# untitled.net
KiCad netlist of a schematic drawn in EAGLE
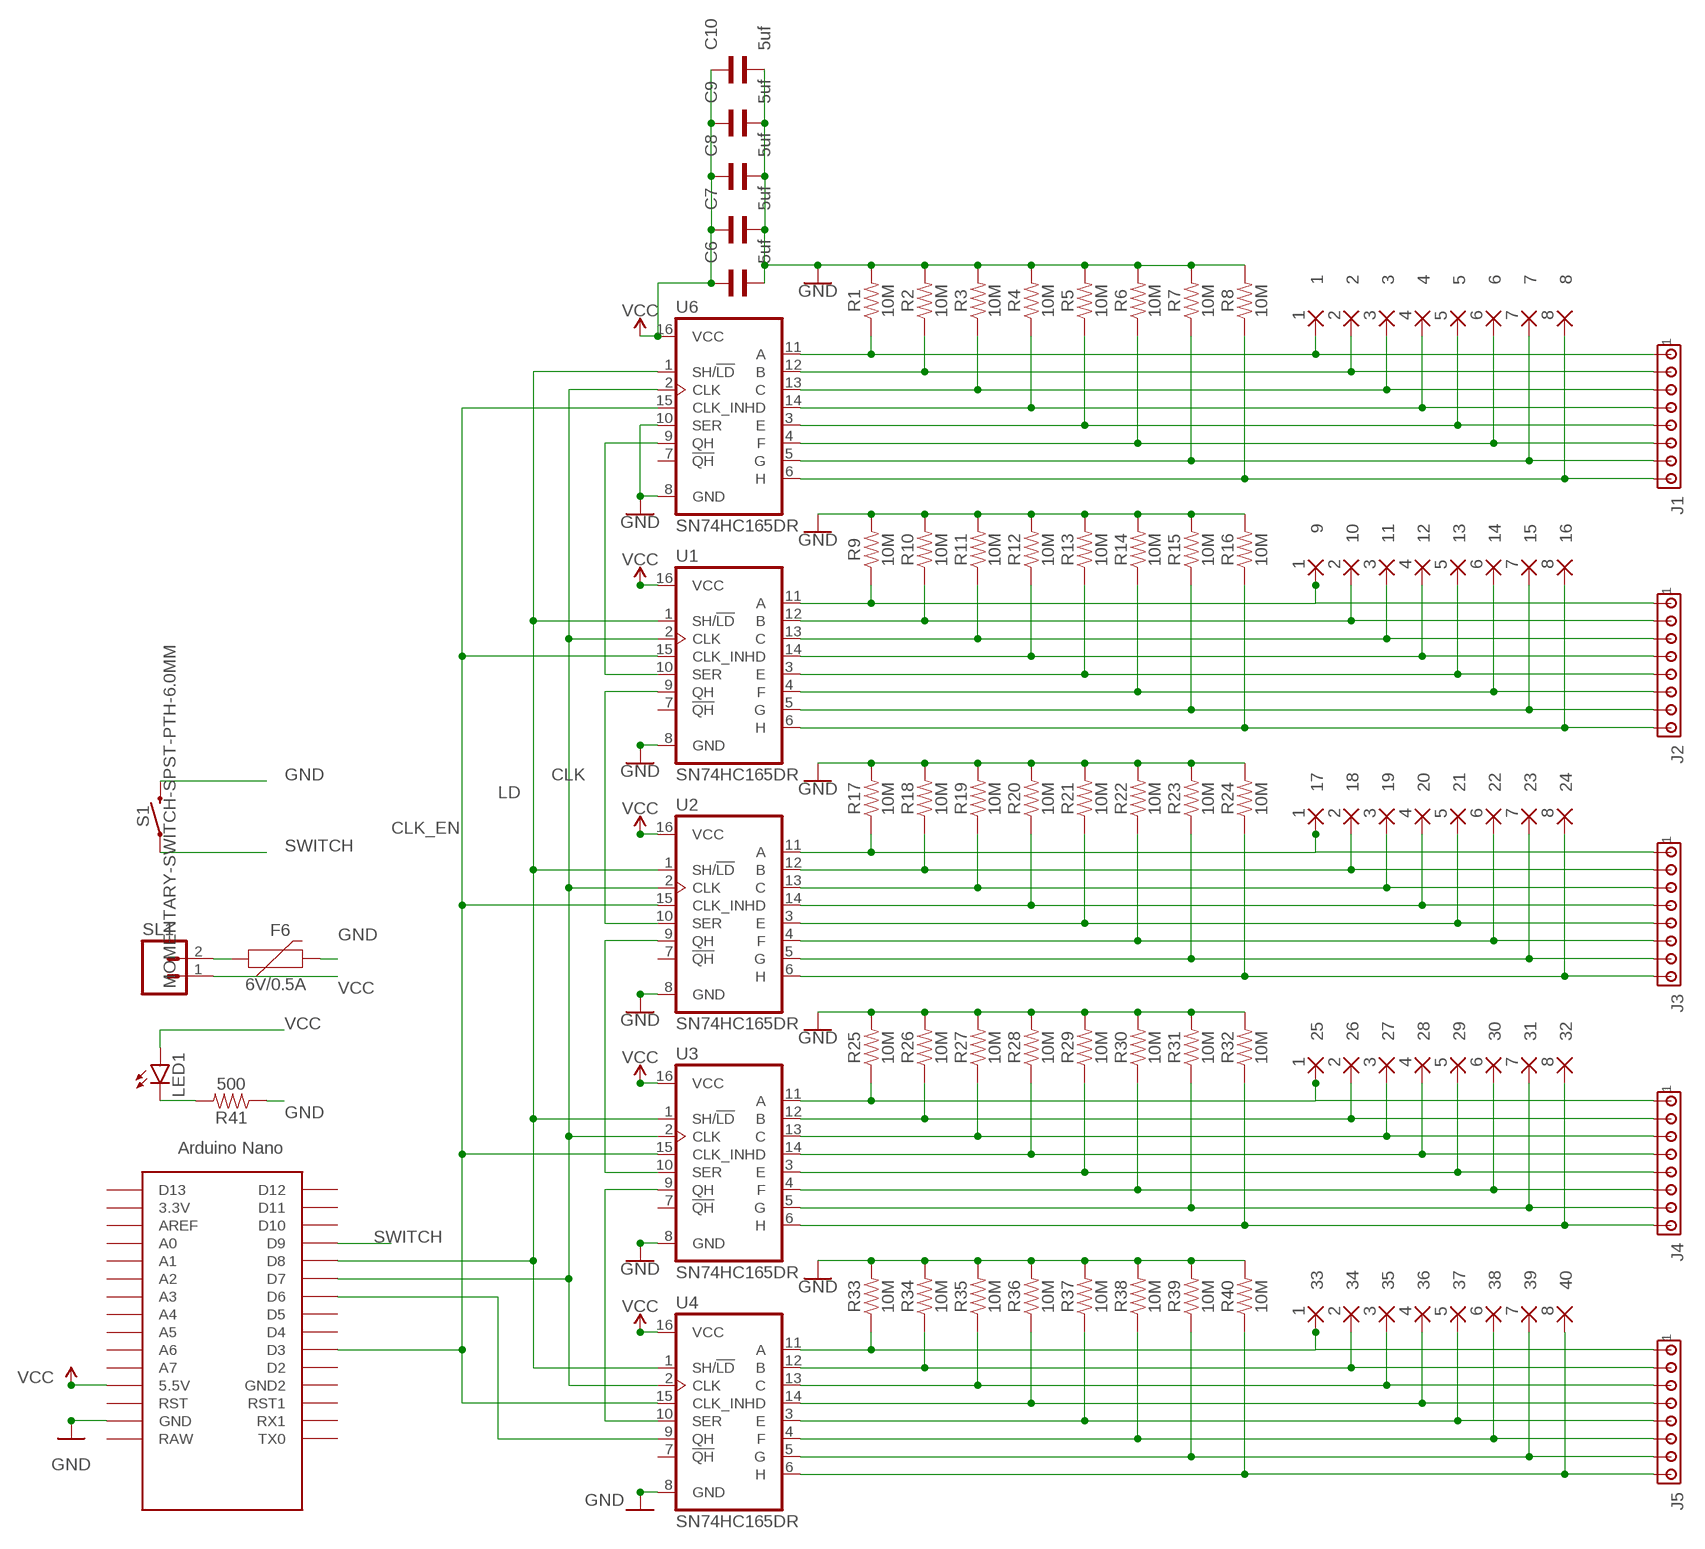
[diagram p0: schematic, sheet 1]

(export (version "E")
  (design (tool "Eeschema 10.0.6"))
  (components
    (comp (ref "1")
      (value "1")
      (footprint "eagle-import:5-1,8")
      (libsource (lib "eagle-import") (part "WIREPADSMD5-1,8"))
    )
    (comp (ref "2")
      (value "2")
      (footprint "eagle-import:5-1,8")
      (libsource (lib "eagle-import") (part "WIREPADSMD5-1,8"))
    )
    (comp (ref "3")
      (value "3")
      (footprint "eagle-import:5-1,8")
      (libsource (lib "eagle-import") (part "WIREPADSMD5-1,8"))
    )
    (comp (ref "4")
      (value "4")
      (footprint "eagle-import:5-1,8")
      (libsource (lib "eagle-import") (part "WIREPADSMD5-1,8"))
    )
    (comp (ref "5")
      (value "5")
      (footprint "eagle-import:5-1,8")
      (libsource (lib "eagle-import") (part "WIREPADSMD5-1,8"))
    )
    (comp (ref "6")
      (value "6")
      (footprint "eagle-import:5-1,8")
      (libsource (lib "eagle-import") (part "WIREPADSMD5-1,8"))
    )
    (comp (ref "7")
      (value "7")
      (footprint "eagle-import:5-1,8")
      (libsource (lib "eagle-import") (part "WIREPADSMD5-1,8"))
    )
    (comp (ref "8")
      (value "8")
      (footprint "eagle-import:5-1,8")
      (libsource (lib "eagle-import") (part "WIREPADSMD5-1,8"))
    )
    (comp (ref "9")
      (value "1")
      (footprint "eagle-import:5-1,8")
      (libsource (lib "eagle-import") (part "WIREPADSMD5-1,8"))
    )
    (comp (ref "10")
      (value "2")
      (footprint "eagle-import:5-1,8")
      (libsource (lib "eagle-import") (part "WIREPADSMD5-1,8"))
    )
    (comp (ref "11")
      (value "3")
      (footprint "eagle-import:5-1,8")
      (libsource (lib "eagle-import") (part "WIREPADSMD5-1,8"))
    )
    (comp (ref "12")
      (value "4")
      (footprint "eagle-import:5-1,8")
      (libsource (lib "eagle-import") (part "WIREPADSMD5-1,8"))
    )
    (comp (ref "13")
      (value "5")
      (footprint "eagle-import:5-1,8")
      (libsource (lib "eagle-import") (part "WIREPADSMD5-1,8"))
    )
    (comp (ref "14")
      (value "6")
      (footprint "eagle-import:5-1,8")
      (libsource (lib "eagle-import") (part "WIREPADSMD5-1,8"))
    )
    (comp (ref "15")
      (value "7")
      (footprint "eagle-import:5-1,8")
      (libsource (lib "eagle-import") (part "WIREPADSMD5-1,8"))
    )
    (comp (ref "16")
      (value "8")
      (footprint "eagle-import:5-1,8")
      (libsource (lib "eagle-import") (part "WIREPADSMD5-1,8"))
    )
    (comp (ref "17")
      (value "1")
      (footprint "eagle-import:5-1,8")
      (libsource (lib "eagle-import") (part "WIREPADSMD5-1,8"))
    )
    (comp (ref "18")
      (value "2")
      (footprint "eagle-import:5-1,8")
      (libsource (lib "eagle-import") (part "WIREPADSMD5-1,8"))
    )
    (comp (ref "19")
      (value "3")
      (footprint "eagle-import:5-1,8")
      (libsource (lib "eagle-import") (part "WIREPADSMD5-1,8"))
    )
    (comp (ref "20")
      (value "4")
      (footprint "eagle-import:5-1,8")
      (libsource (lib "eagle-import") (part "WIREPADSMD5-1,8"))
    )
    (comp (ref "21")
      (value "5")
      (footprint "eagle-import:5-1,8")
      (libsource (lib "eagle-import") (part "WIREPADSMD5-1,8"))
    )
    (comp (ref "22")
      (value "6")
      (footprint "eagle-import:5-1,8")
      (libsource (lib "eagle-import") (part "WIREPADSMD5-1,8"))
    )
    (comp (ref "23")
      (value "7")
      (footprint "eagle-import:5-1,8")
      (libsource (lib "eagle-import") (part "WIREPADSMD5-1,8"))
    )
    (comp (ref "24")
      (value "8")
      (footprint "eagle-import:5-1,8")
      (libsource (lib "eagle-import") (part "WIREPADSMD5-1,8"))
    )
    (comp (ref "25")
      (value "1")
      (footprint "eagle-import:5-1,8")
      (libsource (lib "eagle-import") (part "WIREPADSMD5-1,8"))
    )
    (comp (ref "26")
      (value "2")
      (footprint "eagle-import:5-1,8")
      (libsource (lib "eagle-import") (part "WIREPADSMD5-1,8"))
    )
    (comp (ref "27")
      (value "3")
      (footprint "eagle-import:5-1,8")
      (libsource (lib "eagle-import") (part "WIREPADSMD5-1,8"))
    )
    (comp (ref "28")
      (value "4")
      (footprint "eagle-import:5-1,8")
      (libsource (lib "eagle-import") (part "WIREPADSMD5-1,8"))
    )
    (comp (ref "29")
      (value "5")
      (footprint "eagle-import:5-1,8")
      (libsource (lib "eagle-import") (part "WIREPADSMD5-1,8"))
    )
    (comp (ref "30")
      (value "6")
      (footprint "eagle-import:5-1,8")
      (libsource (lib "eagle-import") (part "WIREPADSMD5-1,8"))
    )
    (comp (ref "31")
      (value "7")
      (footprint "eagle-import:5-1,8")
      (libsource (lib "eagle-import") (part "WIREPADSMD5-1,8"))
    )
    (comp (ref "32")
      (value "8")
      (footprint "eagle-import:5-1,8")
      (libsource (lib "eagle-import") (part "WIREPADSMD5-1,8"))
    )
    (comp (ref "33")
      (value "1")
      (footprint "eagle-import:5-1,8")
      (libsource (lib "eagle-import") (part "WIREPADSMD5-1,8"))
    )
    (comp (ref "34")
      (value "2")
      (footprint "eagle-import:5-1,8")
      (libsource (lib "eagle-import") (part "WIREPADSMD5-1,8"))
    )
    (comp (ref "35")
      (value "3")
      (footprint "eagle-import:5-1,8")
      (libsource (lib "eagle-import") (part "WIREPADSMD5-1,8"))
    )
    (comp (ref "36")
      (value "4")
      (footprint "eagle-import:5-1,8")
      (libsource (lib "eagle-import") (part "WIREPADSMD5-1,8"))
    )
    (comp (ref "37")
      (value "5")
      (footprint "eagle-import:5-1,8")
      (libsource (lib "eagle-import") (part "WIREPADSMD5-1,8"))
    )
    (comp (ref "38")
      (value "6")
      (footprint "eagle-import:5-1,8")
      (libsource (lib "eagle-import") (part "WIREPADSMD5-1,8"))
    )
    (comp (ref "39")
      (value "7")
      (footprint "eagle-import:5-1,8")
      (libsource (lib "eagle-import") (part "WIREPADSMD5-1,8"))
    )
    (comp (ref "40")
      (value "8")
      (footprint "eagle-import:5-1,8")
      (libsource (lib "eagle-import") (part "WIREPADSMD5-1,8"))
    )
    (comp (ref "C6")
      (value "5uf")
      (footprint "eagle-import:WCAP-CSGP_1206")
      (libsource (lib "eagle-import") (part "WCAP-CSGP_1206_885012208119"))
    )
    (comp (ref "C7")
      (value "5uf")
      (footprint "eagle-import:WCAP-CSGP_1206")
      (libsource (lib "eagle-import") (part "WCAP-CSGP_1206_885012208119"))
    )
    (comp (ref "C8")
      (value "5uf")
      (footprint "eagle-import:WCAP-CSGP_1206")
      (libsource (lib "eagle-import") (part "WCAP-CSGP_1206_885012208119"))
    )
    (comp (ref "C9")
      (value "5uf")
      (footprint "eagle-import:WCAP-CSGP_1206")
      (libsource (lib "eagle-import") (part "WCAP-CSGP_1206_885012208119"))
    )
    (comp (ref "C10")
      (value "5uf")
      (footprint "eagle-import:WCAP-CSGP_1206")
      (libsource (lib "eagle-import") (part "WCAP-CSGP_1206_885012208119"))
    )
    (comp (ref "F6")
      (value "6V/0.5A")
      (footprint "eagle-import:1206")
      (libsource (lib "eagle-import") (part "PPTC_HALF-AMP"))
    )
    (comp (ref "J1")
      (value "MTA08-100")
      (footprint "eagle-import:10X08MTA")
      (libsource (lib "eagle-import") (part "MTA08-100"))
    )
    (comp (ref "J2")
      (value "MTA08-100")
      (footprint "eagle-import:10X08MTA")
      (libsource (lib "eagle-import") (part "MTA08-100"))
    )
    (comp (ref "J3")
      (value "MTA08-100")
      (footprint "eagle-import:10X08MTA")
      (libsource (lib "eagle-import") (part "MTA08-100"))
    )
    (comp (ref "J4")
      (value "MTA08-100")
      (footprint "eagle-import:10X08MTA")
      (libsource (lib "eagle-import") (part "MTA08-100"))
    )
    (comp (ref "J5")
      (value "MTA08-100")
      (footprint "eagle-import:10X08MTA")
      (libsource (lib "eagle-import") (part "MTA08-100"))
    )
    (comp (ref "LED1")
      (value "LEDSML0805")
      (footprint "eagle-import:SML0805")
      (libsource (lib "eagle-import") (part "LEDSML0805"))
    )
    (comp (ref "R1")
      (value "10M")
      (footprint "eagle-import:0603")
      (libsource (lib "eagle-import") (part "10MOHM-0603-1/10W-5%"))
    )
    (comp (ref "R2")
      (value "10M")
      (footprint "eagle-import:0603")
      (libsource (lib "eagle-import") (part "10MOHM-0603-1/10W-5%"))
    )
    (comp (ref "R3")
      (value "10M")
      (footprint "eagle-import:0603")
      (libsource (lib "eagle-import") (part "10MOHM-0603-1/10W-5%"))
    )
    (comp (ref "R4")
      (value "10M")
      (footprint "eagle-import:0603")
      (libsource (lib "eagle-import") (part "10MOHM-0603-1/10W-5%"))
    )
    (comp (ref "R5")
      (value "10M")
      (footprint "eagle-import:0603")
      (libsource (lib "eagle-import") (part "10MOHM-0603-1/10W-5%"))
    )
    (comp (ref "R6")
      (value "10M")
      (footprint "eagle-import:0603")
      (libsource (lib "eagle-import") (part "10MOHM-0603-1/10W-5%"))
    )
    (comp (ref "R7")
      (value "10M")
      (footprint "eagle-import:0603")
      (libsource (lib "eagle-import") (part "10MOHM-0603-1/10W-5%"))
    )
    (comp (ref "R8")
      (value "10M")
      (footprint "eagle-import:0603")
      (libsource (lib "eagle-import") (part "10MOHM-0603-1/10W-5%"))
    )
    (comp (ref "R9")
      (value "10M")
      (footprint "eagle-import:0603")
      (libsource (lib "eagle-import") (part "10MOHM-0603-1/10W-5%"))
    )
    (comp (ref "R10")
      (value "10M")
      (footprint "eagle-import:0603")
      (libsource (lib "eagle-import") (part "10MOHM-0603-1/10W-5%"))
    )
    (comp (ref "R11")
      (value "10M")
      (footprint "eagle-import:0603")
      (libsource (lib "eagle-import") (part "10MOHM-0603-1/10W-5%"))
    )
    (comp (ref "R12")
      (value "10M")
      (footprint "eagle-import:0603")
      (libsource (lib "eagle-import") (part "10MOHM-0603-1/10W-5%"))
    )
    (comp (ref "R13")
      (value "10M")
      (footprint "eagle-import:0603")
      (libsource (lib "eagle-import") (part "10MOHM-0603-1/10W-5%"))
    )
    (comp (ref "R14")
      (value "10M")
      (footprint "eagle-import:0603")
      (libsource (lib "eagle-import") (part "10MOHM-0603-1/10W-5%"))
    )
    (comp (ref "R15")
      (value "10M")
      (footprint "eagle-import:0603")
      (libsource (lib "eagle-import") (part "10MOHM-0603-1/10W-5%"))
    )
    (comp (ref "R16")
      (value "10M")
      (footprint "eagle-import:0603")
      (libsource (lib "eagle-import") (part "10MOHM-0603-1/10W-5%"))
    )
    (comp (ref "R17")
      (value "10M")
      (footprint "eagle-import:0603")
      (libsource (lib "eagle-import") (part "10MOHM-0603-1/10W-5%"))
    )
    (comp (ref "R18")
      (value "10M")
      (footprint "eagle-import:0603")
      (libsource (lib "eagle-import") (part "10MOHM-0603-1/10W-5%"))
    )
    (comp (ref "R19")
      (value "10M")
      (footprint "eagle-import:0603")
      (libsource (lib "eagle-import") (part "10MOHM-0603-1/10W-5%"))
    )
    (comp (ref "R20")
      (value "10M")
      (footprint "eagle-import:0603")
      (libsource (lib "eagle-import") (part "10MOHM-0603-1/10W-5%"))
    )
    (comp (ref "R21")
      (value "10M")
      (footprint "eagle-import:0603")
      (libsource (lib "eagle-import") (part "10MOHM-0603-1/10W-5%"))
    )
    (comp (ref "R22")
      (value "10M")
      (footprint "eagle-import:0603")
      (libsource (lib "eagle-import") (part "10MOHM-0603-1/10W-5%"))
    )
    (comp (ref "R23")
      (value "10M")
      (footprint "eagle-import:0603")
      (libsource (lib "eagle-import") (part "10MOHM-0603-1/10W-5%"))
    )
    (comp (ref "R24")
      (value "10M")
      (footprint "eagle-import:0603")
      (libsource (lib "eagle-import") (part "10MOHM-0603-1/10W-5%"))
    )
    (comp (ref "R25")
      (value "10M")
      (footprint "eagle-import:0603")
      (libsource (lib "eagle-import") (part "10MOHM-0603-1/10W-5%"))
    )
    (comp (ref "R26")
      (value "10M")
      (footprint "eagle-import:0603")
      (libsource (lib "eagle-import") (part "10MOHM-0603-1/10W-5%"))
    )
    (comp (ref "R27")
      (value "10M")
      (footprint "eagle-import:0603")
      (libsource (lib "eagle-import") (part "10MOHM-0603-1/10W-5%"))
    )
    (comp (ref "R28")
      (value "10M")
      (footprint "eagle-import:0603")
      (libsource (lib "eagle-import") (part "10MOHM-0603-1/10W-5%"))
    )
    (comp (ref "R29")
      (value "10M")
      (footprint "eagle-import:0603")
      (libsource (lib "eagle-import") (part "10MOHM-0603-1/10W-5%"))
    )
    (comp (ref "R30")
      (value "10M")
      (footprint "eagle-import:0603")
      (libsource (lib "eagle-import") (part "10MOHM-0603-1/10W-5%"))
    )
    (comp (ref "R31")
      (value "10M")
      (footprint "eagle-import:0603")
      (libsource (lib "eagle-import") (part "10MOHM-0603-1/10W-5%"))
    )
    (comp (ref "R32")
      (value "10M")
      (footprint "eagle-import:0603")
      (libsource (lib "eagle-import") (part "10MOHM-0603-1/10W-5%"))
    )
    (comp (ref "R33")
      (value "10M")
      (footprint "eagle-import:0603")
      (libsource (lib "eagle-import") (part "10MOHM-0603-1/10W-5%"))
    )
    (comp (ref "R34")
      (value "10M")
      (footprint "eagle-import:0603")
      (libsource (lib "eagle-import") (part "10MOHM-0603-1/10W-5%"))
    )
    (comp (ref "R35")
      (value "10M")
      (footprint "eagle-import:0603")
      (libsource (lib "eagle-import") (part "10MOHM-0603-1/10W-5%"))
    )
    (comp (ref "R36")
      (value "10M")
      (footprint "eagle-import:0603")
      (libsource (lib "eagle-import") (part "10MOHM-0603-1/10W-5%"))
    )
    (comp (ref "R37")
      (value "10M")
      (footprint "eagle-import:0603")
      (libsource (lib "eagle-import") (part "10MOHM-0603-1/10W-5%"))
    )
    (comp (ref "R38")
      (value "10M")
      (footprint "eagle-import:0603")
      (libsource (lib "eagle-import") (part "10MOHM-0603-1/10W-5%"))
    )
    (comp (ref "R39")
      (value "10M")
      (footprint "eagle-import:0603")
      (libsource (lib "eagle-import") (part "10MOHM-0603-1/10W-5%"))
    )
    (comp (ref "R40")
      (value "10M")
      (footprint "eagle-import:0603")
      (libsource (lib "eagle-import") (part "10MOHM-0603-1/10W-5%"))
    )
    (comp (ref "R41")
      (value "500")
      (footprint "eagle-import:0603")
      (libsource (lib "eagle-import") (part "10MOHM-0603-1/10W-5%"))
    )
    (comp (ref "S1")
      (value "MOMENTARY-SWITCH-SPST-PTH-6.0MM")
      (footprint "eagle-import:TACTILE_SWITCH_PTH_6.0MM")
      (libsource (lib "eagle-import") (part "MOMENTARY-SWITCH-SPST-PTH-6.0MM"))
    )
    (comp (ref "SL1")
      (value "M02")
      (footprint "eagle-import:02P")
      (libsource (lib "eagle-import") (part "M02"))
    )
    (comp (ref "U$1")
      (value "NANO")
      (footprint "eagle-import:NANO")
      (libsource (lib "eagle-import") (part "NANO"))
    )
    (comp (ref "U1")
      (value "SN74HC165DR")
      (footprint "eagle-import:SO16")
      (libsource (lib "eagle-import") (part "74165DHC"))
    )
    (comp (ref "U2")
      (value "SN74HC165DR")
      (footprint "eagle-import:SO16")
      (libsource (lib "eagle-import") (part "74165DHC"))
    )
    (comp (ref "U3")
      (value "SN74HC165DR")
      (footprint "eagle-import:SO16")
      (libsource (lib "eagle-import") (part "74165DHC"))
    )
    (comp (ref "U4")
      (value "SN74HC165DR")
      (footprint "eagle-import:SO16")
      (libsource (lib "eagle-import") (part "74165DHC"))
    )
    (comp (ref "U6")
      (value "SN74HC165DR")
      (footprint "eagle-import:SO16")
      (libsource (lib "eagle-import") (part "74165DHC"))
    )
  )
  (nets
    (net (code "1") (name "/CLK") (class "Default")
      (node (ref "U$1") (pin "D7") (pinfunction "D7_D7") (pintype "bidirectional"))
      (node (ref "U1") (pin "2") (pinfunction "CLK_2") (pintype "input"))
      (node (ref "U2") (pin "2") (pinfunction "CLK_2") (pintype "input"))
      (node (ref "U3") (pin "2") (pinfunction "CLK_2") (pintype "input"))
      (node (ref "U4") (pin "2") (pinfunction "CLK_2") (pintype "input"))
      (node (ref "U6") (pin "2") (pinfunction "CLK_2") (pintype "input"))
    )
    (net (code "2") (name "/CLK_EN") (class "Default")
      (node (ref "U$1") (pin "D3") (pinfunction "D3_D3") (pintype "bidirectional"))
      (node (ref "U1") (pin "15") (pinfunction "CLK_INH_15") (pintype "input"))
      (node (ref "U2") (pin "15") (pinfunction "CLK_INH_15") (pintype "input"))
      (node (ref "U3") (pin "15") (pinfunction "CLK_INH_15") (pintype "input"))
      (node (ref "U4") (pin "15") (pinfunction "CLK_INH_15") (pintype "input"))
      (node (ref "U6") (pin "15") (pinfunction "CLK_INH_15") (pintype "input"))
    )
    (net (code "3") (name "/LD") (class "Default")
      (node (ref "U$1") (pin "D8") (pinfunction "D8_D8") (pintype "bidirectional"))
      (node (ref "U1") (pin "1") (pinfunction "SH/~{LD}_1") (pintype "input"))
      (node (ref "U2") (pin "1") (pinfunction "SH/~{LD}_1") (pintype "input"))
      (node (ref "U3") (pin "1") (pinfunction "SH/~{LD}_1") (pintype "input"))
      (node (ref "U4") (pin "1") (pinfunction "SH/~{LD}_1") (pintype "input"))
      (node (ref "U6") (pin "1") (pinfunction "SH/~{LD}_1") (pintype "input"))
    )
    (net (code "4") (name "/SWITCH") (class "Default")
      (node (ref "S1") (pin "1") (pinfunction "1_1") (pintype "passive"))
      (node (ref "U$1") (pin "D9") (pinfunction "D9_D9") (pintype "bidirectional"))
    )
    (net (code "5") (name "GND") (class "Default")
      (node (ref "C10") (pin "1") (pinfunction "1_1") (pintype "passive"))
      (node (ref "C6") (pin "1") (pinfunction "1_1") (pintype "passive"))
      (node (ref "C7") (pin "1") (pinfunction "1_1") (pintype "passive"))
      (node (ref "C8") (pin "1") (pinfunction "1_1") (pintype "passive"))
      (node (ref "C9") (pin "1") (pinfunction "1_1") (pintype "passive"))
      (node (ref "F6") (pin "2") (pinfunction "2_2") (pintype "bidirectional"))
      (node (ref "R1") (pin "2") (pinfunction "2_2") (pintype "passive"))
      (node (ref "R10") (pin "2") (pinfunction "2_2") (pintype "passive"))
      (node (ref "R11") (pin "2") (pinfunction "2_2") (pintype "passive"))
      (node (ref "R12") (pin "2") (pinfunction "2_2") (pintype "passive"))
      (node (ref "R13") (pin "2") (pinfunction "2_2") (pintype "passive"))
      (node (ref "R14") (pin "2") (pinfunction "2_2") (pintype "passive"))
      (node (ref "R15") (pin "2") (pinfunction "2_2") (pintype "passive"))
      (node (ref "R16") (pin "2") (pinfunction "2_2") (pintype "passive"))
      (node (ref "R17") (pin "2") (pinfunction "2_2") (pintype "passive"))
      (node (ref "R18") (pin "2") (pinfunction "2_2") (pintype "passive"))
      (node (ref "R19") (pin "2") (pinfunction "2_2") (pintype "passive"))
      (node (ref "R2") (pin "2") (pinfunction "2_2") (pintype "passive"))
      (node (ref "R20") (pin "2") (pinfunction "2_2") (pintype "passive"))
      (node (ref "R21") (pin "2") (pinfunction "2_2") (pintype "passive"))
      (node (ref "R22") (pin "2") (pinfunction "2_2") (pintype "passive"))
      (node (ref "R23") (pin "2") (pinfunction "2_2") (pintype "passive"))
      (node (ref "R24") (pin "2") (pinfunction "2_2") (pintype "passive"))
      (node (ref "R25") (pin "2") (pinfunction "2_2") (pintype "passive"))
      (node (ref "R26") (pin "2") (pinfunction "2_2") (pintype "passive"))
      (node (ref "R27") (pin "2") (pinfunction "2_2") (pintype "passive"))
      (node (ref "R28") (pin "2") (pinfunction "2_2") (pintype "passive"))
      (node (ref "R29") (pin "2") (pinfunction "2_2") (pintype "passive"))
      (node (ref "R3") (pin "2") (pinfunction "2_2") (pintype "passive"))
      (node (ref "R30") (pin "2") (pinfunction "2_2") (pintype "passive"))
      (node (ref "R31") (pin "2") (pinfunction "2_2") (pintype "passive"))
      (node (ref "R32") (pin "2") (pinfunction "2_2") (pintype "passive"))
      (node (ref "R33") (pin "2") (pinfunction "2_2") (pintype "passive"))
      (node (ref "R34") (pin "2") (pinfunction "2_2") (pintype "passive"))
      (node (ref "R35") (pin "2") (pinfunction "2_2") (pintype "passive"))
      (node (ref "R36") (pin "2") (pinfunction "2_2") (pintype "passive"))
      (node (ref "R37") (pin "2") (pinfunction "2_2") (pintype "passive"))
      (node (ref "R38") (pin "2") (pinfunction "2_2") (pintype "passive"))
      (node (ref "R39") (pin "2") (pinfunction "2_2") (pintype "passive"))
      (node (ref "R4") (pin "2") (pinfunction "2_2") (pintype "passive"))
      (node (ref "R40") (pin "2") (pinfunction "2_2") (pintype "passive"))
      (node (ref "R41") (pin "1") (pinfunction "1_1") (pintype "passive"))
      (node (ref "R5") (pin "2") (pinfunction "2_2") (pintype "passive"))
      (node (ref "R6") (pin "2") (pinfunction "2_2") (pintype "passive"))
      (node (ref "R7") (pin "2") (pinfunction "2_2") (pintype "passive"))
      (node (ref "R8") (pin "2") (pinfunction "2_2") (pintype "passive"))
      (node (ref "R9") (pin "2") (pinfunction "2_2") (pintype "passive"))
      (node (ref "S1") (pin "3") (pinfunction "2_3") (pintype "passive"))
      (node (ref "U$1") (pin "GND") (pinfunction "GND_GND") (pintype "bidirectional"))
      (node (ref "U1") (pin "8") (pinfunction "GND_8") (pintype "power_in"))
      (node (ref "U2") (pin "8") (pinfunction "GND_8") (pintype "power_in"))
      (node (ref "U3") (pin "8") (pinfunction "GND_8") (pintype "power_in"))
      (node (ref "U4") (pin "8") (pinfunction "GND_8") (pintype "power_in"))
      (node (ref "U6") (pin "10") (pinfunction "SER_10") (pintype "input"))
      (node (ref "U6") (pin "8") (pinfunction "GND_8") (pintype "power_in"))
    )
    (net (code "6") (name "Net-(1-P)") (class "Default")
      (node (ref "1") (pin "1") (pinfunction "P_1") (pintype "passive"))
      (node (ref "J1") (pin "1") (pinfunction "1_1") (pintype "passive"))
      (node (ref "R1") (pin "1") (pinfunction "1_1") (pintype "passive"))
      (node (ref "U6") (pin "11") (pinfunction "A_11") (pintype "tri_state"))
    )
    (net (code "7") (name "Net-(2-P)") (class "Default")
      (node (ref "2") (pin "1") (pinfunction "P_1") (pintype "passive"))
      (node (ref "J1") (pin "2") (pinfunction "2_2") (pintype "passive"))
      (node (ref "R2") (pin "1") (pinfunction "1_1") (pintype "passive"))
      (node (ref "U6") (pin "12") (pinfunction "B_12") (pintype "tri_state"))
    )
    (net (code "8") (name "Net-(3-P)") (class "Default")
      (node (ref "3") (pin "1") (pinfunction "P_1") (pintype "passive"))
      (node (ref "J1") (pin "3") (pinfunction "3_3") (pintype "passive"))
      (node (ref "R3") (pin "1") (pinfunction "1_1") (pintype "passive"))
      (node (ref "U6") (pin "13") (pinfunction "C_13") (pintype "tri_state"))
    )
    (net (code "9") (name "Net-(4-P)") (class "Default")
      (node (ref "4") (pin "1") (pinfunction "P_1") (pintype "passive"))
      (node (ref "J1") (pin "4") (pinfunction "4_4") (pintype "passive"))
      (node (ref "R4") (pin "1") (pinfunction "1_1") (pintype "passive"))
      (node (ref "U6") (pin "14") (pinfunction "D_14") (pintype "tri_state"))
    )
    (net (code "10") (name "Net-(5-P)") (class "Default")
      (node (ref "5") (pin "1") (pinfunction "P_1") (pintype "passive"))
      (node (ref "J1") (pin "5") (pinfunction "5_5") (pintype "passive"))
      (node (ref "R5") (pin "1") (pinfunction "1_1") (pintype "passive"))
      (node (ref "U6") (pin "3") (pinfunction "E_3") (pintype "tri_state"))
    )
    (net (code "11") (name "Net-(6-P)") (class "Default")
      (node (ref "6") (pin "1") (pinfunction "P_1") (pintype "passive"))
      (node (ref "J1") (pin "6") (pinfunction "6_6") (pintype "passive"))
      (node (ref "R6") (pin "1") (pinfunction "1_1") (pintype "passive"))
      (node (ref "U6") (pin "4") (pinfunction "F_4") (pintype "tri_state"))
    )
    (net (code "12") (name "Net-(7-P)") (class "Default")
      (node (ref "7") (pin "1") (pinfunction "P_1") (pintype "passive"))
      (node (ref "J1") (pin "7") (pinfunction "7_7") (pintype "passive"))
      (node (ref "R7") (pin "1") (pinfunction "1_1") (pintype "passive"))
      (node (ref "U6") (pin "5") (pinfunction "G_5") (pintype "tri_state"))
    )
    (net (code "13") (name "Net-(8-P)") (class "Default")
      (node (ref "8") (pin "1") (pinfunction "P_1") (pintype "passive"))
      (node (ref "J1") (pin "8") (pinfunction "8_8") (pintype "passive"))
      (node (ref "R8") (pin "1") (pinfunction "1_1") (pintype "passive"))
      (node (ref "U6") (pin "6") (pinfunction "H_6") (pintype "tri_state"))
    )
    (net (code "14") (name "Net-(9-P)") (class "Default")
      (node (ref "9") (pin "1") (pinfunction "P_1") (pintype "passive"))
      (node (ref "J2") (pin "1") (pinfunction "1_1") (pintype "passive"))
      (node (ref "R9") (pin "1") (pinfunction "1_1") (pintype "passive"))
      (node (ref "U1") (pin "11") (pinfunction "A_11") (pintype "tri_state"))
    )
    (net (code "15") (name "Net-(10-P)") (class "Default")
      (node (ref "10") (pin "1") (pinfunction "P_1") (pintype "passive"))
      (node (ref "J2") (pin "2") (pinfunction "2_2") (pintype "passive"))
      (node (ref "R10") (pin "1") (pinfunction "1_1") (pintype "passive"))
      (node (ref "U1") (pin "12") (pinfunction "B_12") (pintype "tri_state"))
    )
    (net (code "16") (name "Net-(11-P)") (class "Default")
      (node (ref "11") (pin "1") (pinfunction "P_1") (pintype "passive"))
      (node (ref "J2") (pin "3") (pinfunction "3_3") (pintype "passive"))
      (node (ref "R11") (pin "1") (pinfunction "1_1") (pintype "passive"))
      (node (ref "U1") (pin "13") (pinfunction "C_13") (pintype "tri_state"))
    )
    (net (code "17") (name "Net-(12-P)") (class "Default")
      (node (ref "12") (pin "1") (pinfunction "P_1") (pintype "passive"))
      (node (ref "J2") (pin "4") (pinfunction "4_4") (pintype "passive"))
      (node (ref "R12") (pin "1") (pinfunction "1_1") (pintype "passive"))
      (node (ref "U1") (pin "14") (pinfunction "D_14") (pintype "tri_state"))
    )
    (net (code "18") (name "Net-(13-P)") (class "Default")
      (node (ref "13") (pin "1") (pinfunction "P_1") (pintype "passive"))
      (node (ref "J2") (pin "5") (pinfunction "5_5") (pintype "passive"))
      (node (ref "R13") (pin "1") (pinfunction "1_1") (pintype "passive"))
      (node (ref "U1") (pin "3") (pinfunction "E_3") (pintype "tri_state"))
    )
    (net (code "19") (name "Net-(14-P)") (class "Default")
      (node (ref "14") (pin "1") (pinfunction "P_1") (pintype "passive"))
      (node (ref "J2") (pin "6") (pinfunction "6_6") (pintype "passive"))
      (node (ref "R14") (pin "1") (pinfunction "1_1") (pintype "passive"))
      (node (ref "U1") (pin "4") (pinfunction "F_4") (pintype "tri_state"))
    )
    (net (code "20") (name "Net-(15-P)") (class "Default")
      (node (ref "15") (pin "1") (pinfunction "P_1") (pintype "passive"))
      (node (ref "J2") (pin "7") (pinfunction "7_7") (pintype "passive"))
      (node (ref "R15") (pin "1") (pinfunction "1_1") (pintype "passive"))
      (node (ref "U1") (pin "5") (pinfunction "G_5") (pintype "tri_state"))
    )
    (net (code "21") (name "Net-(16-P)") (class "Default")
      (node (ref "16") (pin "1") (pinfunction "P_1") (pintype "passive"))
      (node (ref "J2") (pin "8") (pinfunction "8_8") (pintype "passive"))
      (node (ref "R16") (pin "1") (pinfunction "1_1") (pintype "passive"))
      (node (ref "U1") (pin "6") (pinfunction "H_6") (pintype "tri_state"))
    )
    (net (code "22") (name "Net-(17-P)") (class "Default")
      (node (ref "17") (pin "1") (pinfunction "P_1") (pintype "passive"))
      (node (ref "J3") (pin "1") (pinfunction "1_1") (pintype "passive"))
      (node (ref "R17") (pin "1") (pinfunction "1_1") (pintype "passive"))
      (node (ref "U2") (pin "11") (pinfunction "A_11") (pintype "tri_state"))
    )
    (net (code "23") (name "Net-(18-P)") (class "Default")
      (node (ref "18") (pin "1") (pinfunction "P_1") (pintype "passive"))
      (node (ref "J3") (pin "2") (pinfunction "2_2") (pintype "passive"))
      (node (ref "R18") (pin "1") (pinfunction "1_1") (pintype "passive"))
      (node (ref "U2") (pin "12") (pinfunction "B_12") (pintype "tri_state"))
    )
    (net (code "24") (name "Net-(19-P)") (class "Default")
      (node (ref "19") (pin "1") (pinfunction "P_1") (pintype "passive"))
      (node (ref "J3") (pin "3") (pinfunction "3_3") (pintype "passive"))
      (node (ref "R19") (pin "1") (pinfunction "1_1") (pintype "passive"))
      (node (ref "U2") (pin "13") (pinfunction "C_13") (pintype "tri_state"))
    )
    (net (code "25") (name "Net-(20-P)") (class "Default")
      (node (ref "20") (pin "1") (pinfunction "P_1") (pintype "passive"))
      (node (ref "J3") (pin "4") (pinfunction "4_4") (pintype "passive"))
      (node (ref "R20") (pin "1") (pinfunction "1_1") (pintype "passive"))
      (node (ref "U2") (pin "14") (pinfunction "D_14") (pintype "tri_state"))
    )
    (net (code "26") (name "Net-(21-P)") (class "Default")
      (node (ref "21") (pin "1") (pinfunction "P_1") (pintype "passive"))
      (node (ref "J3") (pin "5") (pinfunction "5_5") (pintype "passive"))
      (node (ref "R21") (pin "1") (pinfunction "1_1") (pintype "passive"))
      (node (ref "U2") (pin "3") (pinfunction "E_3") (pintype "tri_state"))
    )
    (net (code "27") (name "Net-(22-P)") (class "Default")
      (node (ref "22") (pin "1") (pinfunction "P_1") (pintype "passive"))
      (node (ref "J3") (pin "6") (pinfunction "6_6") (pintype "passive"))
      (node (ref "R22") (pin "1") (pinfunction "1_1") (pintype "passive"))
      (node (ref "U2") (pin "4") (pinfunction "F_4") (pintype "tri_state"))
    )
    (net (code "28") (name "Net-(23-P)") (class "Default")
      (node (ref "23") (pin "1") (pinfunction "P_1") (pintype "passive"))
      (node (ref "J3") (pin "7") (pinfunction "7_7") (pintype "passive"))
      (node (ref "R23") (pin "1") (pinfunction "1_1") (pintype "passive"))
      (node (ref "U2") (pin "5") (pinfunction "G_5") (pintype "tri_state"))
    )
    (net (code "29") (name "Net-(24-P)") (class "Default")
      (node (ref "24") (pin "1") (pinfunction "P_1") (pintype "passive"))
      (node (ref "J3") (pin "8") (pinfunction "8_8") (pintype "passive"))
      (node (ref "R24") (pin "1") (pinfunction "1_1") (pintype "passive"))
      (node (ref "U2") (pin "6") (pinfunction "H_6") (pintype "tri_state"))
    )
    (net (code "30") (name "Net-(25-P)") (class "Default")
      (node (ref "25") (pin "1") (pinfunction "P_1") (pintype "passive"))
      (node (ref "J4") (pin "1") (pinfunction "1_1") (pintype "passive"))
      (node (ref "R25") (pin "1") (pinfunction "1_1") (pintype "passive"))
      (node (ref "U3") (pin "11") (pinfunction "A_11") (pintype "tri_state"))
    )
    (net (code "31") (name "Net-(26-P)") (class "Default")
      (node (ref "26") (pin "1") (pinfunction "P_1") (pintype "passive"))
      (node (ref "J4") (pin "2") (pinfunction "2_2") (pintype "passive"))
      (node (ref "R26") (pin "1") (pinfunction "1_1") (pintype "passive"))
      (node (ref "U3") (pin "12") (pinfunction "B_12") (pintype "tri_state"))
    )
    (net (code "32") (name "Net-(27-P)") (class "Default")
      (node (ref "27") (pin "1") (pinfunction "P_1") (pintype "passive"))
      (node (ref "J4") (pin "3") (pinfunction "3_3") (pintype "passive"))
      (node (ref "R27") (pin "1") (pinfunction "1_1") (pintype "passive"))
      (node (ref "U3") (pin "13") (pinfunction "C_13") (pintype "tri_state"))
    )
    (net (code "33") (name "Net-(28-P)") (class "Default")
      (node (ref "28") (pin "1") (pinfunction "P_1") (pintype "passive"))
      (node (ref "J4") (pin "4") (pinfunction "4_4") (pintype "passive"))
      (node (ref "R28") (pin "1") (pinfunction "1_1") (pintype "passive"))
      (node (ref "U3") (pin "14") (pinfunction "D_14") (pintype "tri_state"))
    )
    (net (code "34") (name "Net-(29-P)") (class "Default")
      (node (ref "29") (pin "1") (pinfunction "P_1") (pintype "passive"))
      (node (ref "J4") (pin "5") (pinfunction "5_5") (pintype "passive"))
      (node (ref "R29") (pin "1") (pinfunction "1_1") (pintype "passive"))
      (node (ref "U3") (pin "3") (pinfunction "E_3") (pintype "tri_state"))
    )
    (net (code "35") (name "Net-(30-P)") (class "Default")
      (node (ref "30") (pin "1") (pinfunction "P_1") (pintype "passive"))
      (node (ref "J4") (pin "6") (pinfunction "6_6") (pintype "passive"))
      (node (ref "R30") (pin "1") (pinfunction "1_1") (pintype "passive"))
      (node (ref "U3") (pin "4") (pinfunction "F_4") (pintype "tri_state"))
    )
    (net (code "36") (name "Net-(31-P)") (class "Default")
      (node (ref "31") (pin "1") (pinfunction "P_1") (pintype "passive"))
      (node (ref "J4") (pin "7") (pinfunction "7_7") (pintype "passive"))
      (node (ref "R31") (pin "1") (pinfunction "1_1") (pintype "passive"))
      (node (ref "U3") (pin "5") (pinfunction "G_5") (pintype "tri_state"))
    )
    (net (code "37") (name "Net-(32-P)") (class "Default")
      (node (ref "32") (pin "1") (pinfunction "P_1") (pintype "passive"))
      (node (ref "J4") (pin "8") (pinfunction "8_8") (pintype "passive"))
      (node (ref "R32") (pin "1") (pinfunction "1_1") (pintype "passive"))
      (node (ref "U3") (pin "6") (pinfunction "H_6") (pintype "tri_state"))
    )
    (net (code "38") (name "Net-(33-P)") (class "Default")
      (node (ref "33") (pin "1") (pinfunction "P_1") (pintype "passive"))
      (node (ref "J5") (pin "1") (pinfunction "1_1") (pintype "passive"))
      (node (ref "R33") (pin "1") (pinfunction "1_1") (pintype "passive"))
      (node (ref "U4") (pin "11") (pinfunction "A_11") (pintype "tri_state"))
    )
    (net (code "39") (name "Net-(34-P)") (class "Default")
      (node (ref "34") (pin "1") (pinfunction "P_1") (pintype "passive"))
      (node (ref "J5") (pin "2") (pinfunction "2_2") (pintype "passive"))
      (node (ref "R34") (pin "1") (pinfunction "1_1") (pintype "passive"))
      (node (ref "U4") (pin "12") (pinfunction "B_12") (pintype "tri_state"))
    )
    (net (code "40") (name "Net-(35-P)") (class "Default")
      (node (ref "35") (pin "1") (pinfunction "P_1") (pintype "passive"))
      (node (ref "J5") (pin "3") (pinfunction "3_3") (pintype "passive"))
      (node (ref "R35") (pin "1") (pinfunction "1_1") (pintype "passive"))
      (node (ref "U4") (pin "13") (pinfunction "C_13") (pintype "tri_state"))
    )
    (net (code "41") (name "Net-(36-P)") (class "Default")
      (node (ref "36") (pin "1") (pinfunction "P_1") (pintype "passive"))
      (node (ref "J5") (pin "4") (pinfunction "4_4") (pintype "passive"))
      (node (ref "R36") (pin "1") (pinfunction "1_1") (pintype "passive"))
      (node (ref "U4") (pin "14") (pinfunction "D_14") (pintype "tri_state"))
    )
    (net (code "42") (name "Net-(37-P)") (class "Default")
      (node (ref "37") (pin "1") (pinfunction "P_1") (pintype "passive"))
      (node (ref "J5") (pin "5") (pinfunction "5_5") (pintype "passive"))
      (node (ref "R37") (pin "1") (pinfunction "1_1") (pintype "passive"))
      (node (ref "U4") (pin "3") (pinfunction "E_3") (pintype "tri_state"))
    )
    (net (code "43") (name "Net-(38-P)") (class "Default")
      (node (ref "38") (pin "1") (pinfunction "P_1") (pintype "passive"))
      (node (ref "J5") (pin "6") (pinfunction "6_6") (pintype "passive"))
      (node (ref "R38") (pin "1") (pinfunction "1_1") (pintype "passive"))
      (node (ref "U4") (pin "4") (pinfunction "F_4") (pintype "tri_state"))
    )
    (net (code "44") (name "Net-(39-P)") (class "Default")
      (node (ref "39") (pin "1") (pinfunction "P_1") (pintype "passive"))
      (node (ref "J5") (pin "7") (pinfunction "7_7") (pintype "passive"))
      (node (ref "R39") (pin "1") (pinfunction "1_1") (pintype "passive"))
      (node (ref "U4") (pin "5") (pinfunction "G_5") (pintype "tri_state"))
    )
    (net (code "45") (name "Net-(40-P)") (class "Default")
      (node (ref "40") (pin "1") (pinfunction "P_1") (pintype "passive"))
      (node (ref "J5") (pin "8") (pinfunction "8_8") (pintype "passive"))
      (node (ref "R40") (pin "1") (pinfunction "1_1") (pintype "passive"))
      (node (ref "U4") (pin "6") (pinfunction "H_6") (pintype "tri_state"))
    )
    (net (code "46") (name "Net-(F6-Pad1)") (class "Default")
      (node (ref "F6") (pin "1") (pinfunction "1_1") (pintype "bidirectional"))
      (node (ref "SL1") (pin "2") (pinfunction "2_2") (pintype "passive"))
    )
    (net (code "47") (name "Net-(LED1-PadC)") (class "Default")
      (node (ref "LED1") (pin "C") (pinfunction "C_C") (pintype "passive"))
      (node (ref "R41") (pin "2") (pinfunction "2_2") (pintype "passive"))
    )
    (net (code "48") (name "Net-(U1-QH)") (class "Default")
      (node (ref "U1") (pin "9") (pinfunction "QH_9") (pintype "tri_state"))
      (node (ref "U2") (pin "10") (pinfunction "SER_10") (pintype "input"))
    )
    (net (code "49") (name "Net-(U1-SER)") (class "Default")
      (node (ref "U1") (pin "10") (pinfunction "SER_10") (pintype "input"))
      (node (ref "U6") (pin "9") (pinfunction "QH_9") (pintype "tri_state"))
    )
    (net (code "50") (name "Net-(U2-QH)") (class "Default")
      (node (ref "U2") (pin "9") (pinfunction "QH_9") (pintype "tri_state"))
      (node (ref "U3") (pin "10") (pinfunction "SER_10") (pintype "input"))
    )
    (net (code "51") (name "Net-(U3-QH)") (class "Default")
      (node (ref "U3") (pin "9") (pinfunction "QH_9") (pintype "tri_state"))
      (node (ref "U4") (pin "10") (pinfunction "SER_10") (pintype "input"))
    )
    (net (code "52") (name "Net-(U4-QH)") (class "Default")
      (node (ref "U$1") (pin "D6") (pinfunction "D6_D6") (pintype "bidirectional"))
      (node (ref "U4") (pin "9") (pinfunction "QH_9") (pintype "tri_state"))
    )
    (net (code "53") (name "VCC") (class "Default")
      (node (ref "C10") (pin "2") (pinfunction "2_2") (pintype "passive"))
      (node (ref "C6") (pin "2") (pinfunction "2_2") (pintype "passive"))
      (node (ref "C7") (pin "2") (pinfunction "2_2") (pintype "passive"))
      (node (ref "C8") (pin "2") (pinfunction "2_2") (pintype "passive"))
      (node (ref "C9") (pin "2") (pinfunction "2_2") (pintype "passive"))
      (node (ref "LED1") (pin "A") (pinfunction "A_A") (pintype "passive"))
      (node (ref "SL1") (pin "1") (pinfunction "1_1") (pintype "passive"))
      (node (ref "U$1") (pin "5V") (pinfunction "5.5V_5V") (pintype "bidirectional"))
      (node (ref "U1") (pin "16") (pinfunction "VCC_16") (pintype "power_in"))
      (node (ref "U2") (pin "16") (pinfunction "VCC_16") (pintype "power_in"))
      (node (ref "U3") (pin "16") (pinfunction "VCC_16") (pintype "power_in"))
      (node (ref "U4") (pin "16") (pinfunction "VCC_16") (pintype "power_in"))
      (node (ref "U6") (pin "16") (pinfunction "VCC_16") (pintype "power_in"))
    )
    (net (code "54") (name "unconnected-(U$1-GND2-PadGND1)") (class "Default")
      (node (ref "U$1") (pin "GND1") (pinfunction "GND2_GND1") (pintype "bidirectional"))
    )
    (net (code "55") (name "unconnected-(U$1-Pad3.3V)") (class "Default")
      (node (ref "U$1") (pin "3.3V") (pinfunction "3.3V_3.3V") (pintype "bidirectional"))
    )
    (net (code "56") (name "unconnected-(U$1-PadA0)") (class "Default")
      (node (ref "U$1") (pin "A0") (pinfunction "A0_A0") (pintype "bidirectional"))
    )
    (net (code "57") (name "unconnected-(U$1-PadA1)") (class "Default")
      (node (ref "U$1") (pin "A1") (pinfunction "A1_A1") (pintype "bidirectional"))
    )
    (net (code "58") (name "unconnected-(U$1-PadA2)") (class "Default")
      (node (ref "U$1") (pin "A2") (pinfunction "A2_A2") (pintype "bidirectional"))
    )
    (net (code "59") (name "unconnected-(U$1-PadA3)") (class "Default")
      (node (ref "U$1") (pin "A3") (pinfunction "A3_A3") (pintype "bidirectional"))
    )
    (net (code "60") (name "unconnected-(U$1-PadA4)") (class "Default")
      (node (ref "U$1") (pin "A4") (pinfunction "A4_A4") (pintype "bidirectional"))
    )
    (net (code "61") (name "unconnected-(U$1-PadA5)") (class "Default")
      (node (ref "U$1") (pin "A5") (pinfunction "A5_A5") (pintype "bidirectional"))
    )
    (net (code "62") (name "unconnected-(U$1-PadA6)") (class "Default")
      (node (ref "U$1") (pin "A6") (pinfunction "A6_A6") (pintype "bidirectional"))
    )
    (net (code "63") (name "unconnected-(U$1-PadA7)") (class "Default")
      (node (ref "U$1") (pin "A7") (pinfunction "A7_A7") (pintype "bidirectional"))
    )
    (net (code "64") (name "unconnected-(U$1-PadAREF)") (class "Default")
      (node (ref "U$1") (pin "AREF") (pinfunction "AREF_AREF") (pintype "bidirectional"))
    )
    (net (code "65") (name "unconnected-(U$1-PadD2)") (class "Default")
      (node (ref "U$1") (pin "D2") (pinfunction "D2_D2") (pintype "bidirectional"))
    )
    (net (code "66") (name "unconnected-(U$1-PadD4)") (class "Default")
      (node (ref "U$1") (pin "D4") (pinfunction "D4_D4") (pintype "bidirectional"))
    )
    (net (code "67") (name "unconnected-(U$1-PadD5)") (class "Default")
      (node (ref "U$1") (pin "D5") (pinfunction "D5_D5") (pintype "bidirectional"))
    )
    (net (code "68") (name "unconnected-(U$1-PadD10)") (class "Default")
      (node (ref "U$1") (pin "D10") (pinfunction "D10_D10") (pintype "bidirectional"))
    )
    (net (code "69") (name "unconnected-(U$1-PadD11)") (class "Default")
      (node (ref "U$1") (pin "D11") (pinfunction "D11_D11") (pintype "bidirectional"))
    )
    (net (code "70") (name "unconnected-(U$1-PadD12)") (class "Default")
      (node (ref "U$1") (pin "D12") (pinfunction "D12_D12") (pintype "bidirectional"))
    )
    (net (code "71") (name "unconnected-(U$1-PadD13)") (class "Default")
      (node (ref "U$1") (pin "D13") (pinfunction "D13_D13") (pintype "bidirectional"))
    )
    (net (code "72") (name "unconnected-(U$1-PadICSP1)") (class "Default")
      (node (ref "U$1") (pin "ICSP1") (pinfunction "ICSP1_ICSP1") (pintype "bidirectional"))
    )
    (net (code "73") (name "unconnected-(U$1-PadICSP2)") (class "Default")
      (node (ref "U$1") (pin "ICSP2") (pinfunction "ICSP2_ICSP2") (pintype "bidirectional"))
    )
    (net (code "74") (name "unconnected-(U$1-PadICSP3)") (class "Default")
      (node (ref "U$1") (pin "ICSP3") (pinfunction "ICSP3_ICSP3") (pintype "bidirectional"))
    )
    (net (code "75") (name "unconnected-(U$1-PadICSP4)") (class "Default")
      (node (ref "U$1") (pin "ICSP4") (pinfunction "ICSP4_ICSP4") (pintype "bidirectional"))
    )
    (net (code "76") (name "unconnected-(U$1-PadICSP5)") (class "Default")
      (node (ref "U$1") (pin "ICSP5") (pinfunction "ICSP5_ICSP5") (pintype "bidirectional"))
    )
    (net (code "77") (name "unconnected-(U$1-PadICSP6)") (class "Default")
      (node (ref "U$1") (pin "ICSP6") (pinfunction "ICSP6_ICSP6") (pintype "bidirectional"))
    )
    (net (code "78") (name "unconnected-(U$1-PadRAW)") (class "Default")
      (node (ref "U$1") (pin "RAW") (pinfunction "RAW_RAW") (pintype "bidirectional"))
    )
    (net (code "79") (name "unconnected-(U$1-PadRST)") (class "Default")
      (node (ref "U$1") (pin "RST") (pinfunction "RST_RST") (pintype "bidirectional"))
    )
    (net (code "80") (name "unconnected-(U$1-PadRST1)") (class "Default")
      (node (ref "U$1") (pin "RST1") (pinfunction "RST1_RST1") (pintype "bidirectional"))
    )
    (net (code "81") (name "unconnected-(U$1-PadRX1)") (class "Default")
      (node (ref "U$1") (pin "RX1") (pinfunction "RX1_RX1") (pintype "bidirectional"))
    )
    (net (code "82") (name "unconnected-(U$1-PadTX0)") (class "Default")
      (node (ref "U$1") (pin "TX0") (pinfunction "TX0_TX0") (pintype "bidirectional"))
    )
    (net (code "83") (name "unconnected-(U1-~{QH}-Pad7)") (class "Default")
      (node (ref "U1") (pin "7") (pinfunction "~{QH}_7") (pintype "input"))
    )
    (net (code "84") (name "unconnected-(U2-~{QH}-Pad7)") (class "Default")
      (node (ref "U2") (pin "7") (pinfunction "~{QH}_7") (pintype "input"))
    )
    (net (code "85") (name "unconnected-(U3-~{QH}-Pad7)") (class "Default")
      (node (ref "U3") (pin "7") (pinfunction "~{QH}_7") (pintype "input"))
    )
    (net (code "86") (name "unconnected-(U4-~{QH}-Pad7)") (class "Default")
      (node (ref "U4") (pin "7") (pinfunction "~{QH}_7") (pintype "input"))
    )
    (net (code "87") (name "unconnected-(U6-~{QH}-Pad7)") (class "Default")
      (node (ref "U6") (pin "7") (pinfunction "~{QH}_7") (pintype "input"))
    )
  )
)
